# BOB_v1_03.net
KiCad netlist of a schematic drawn in EAGLE
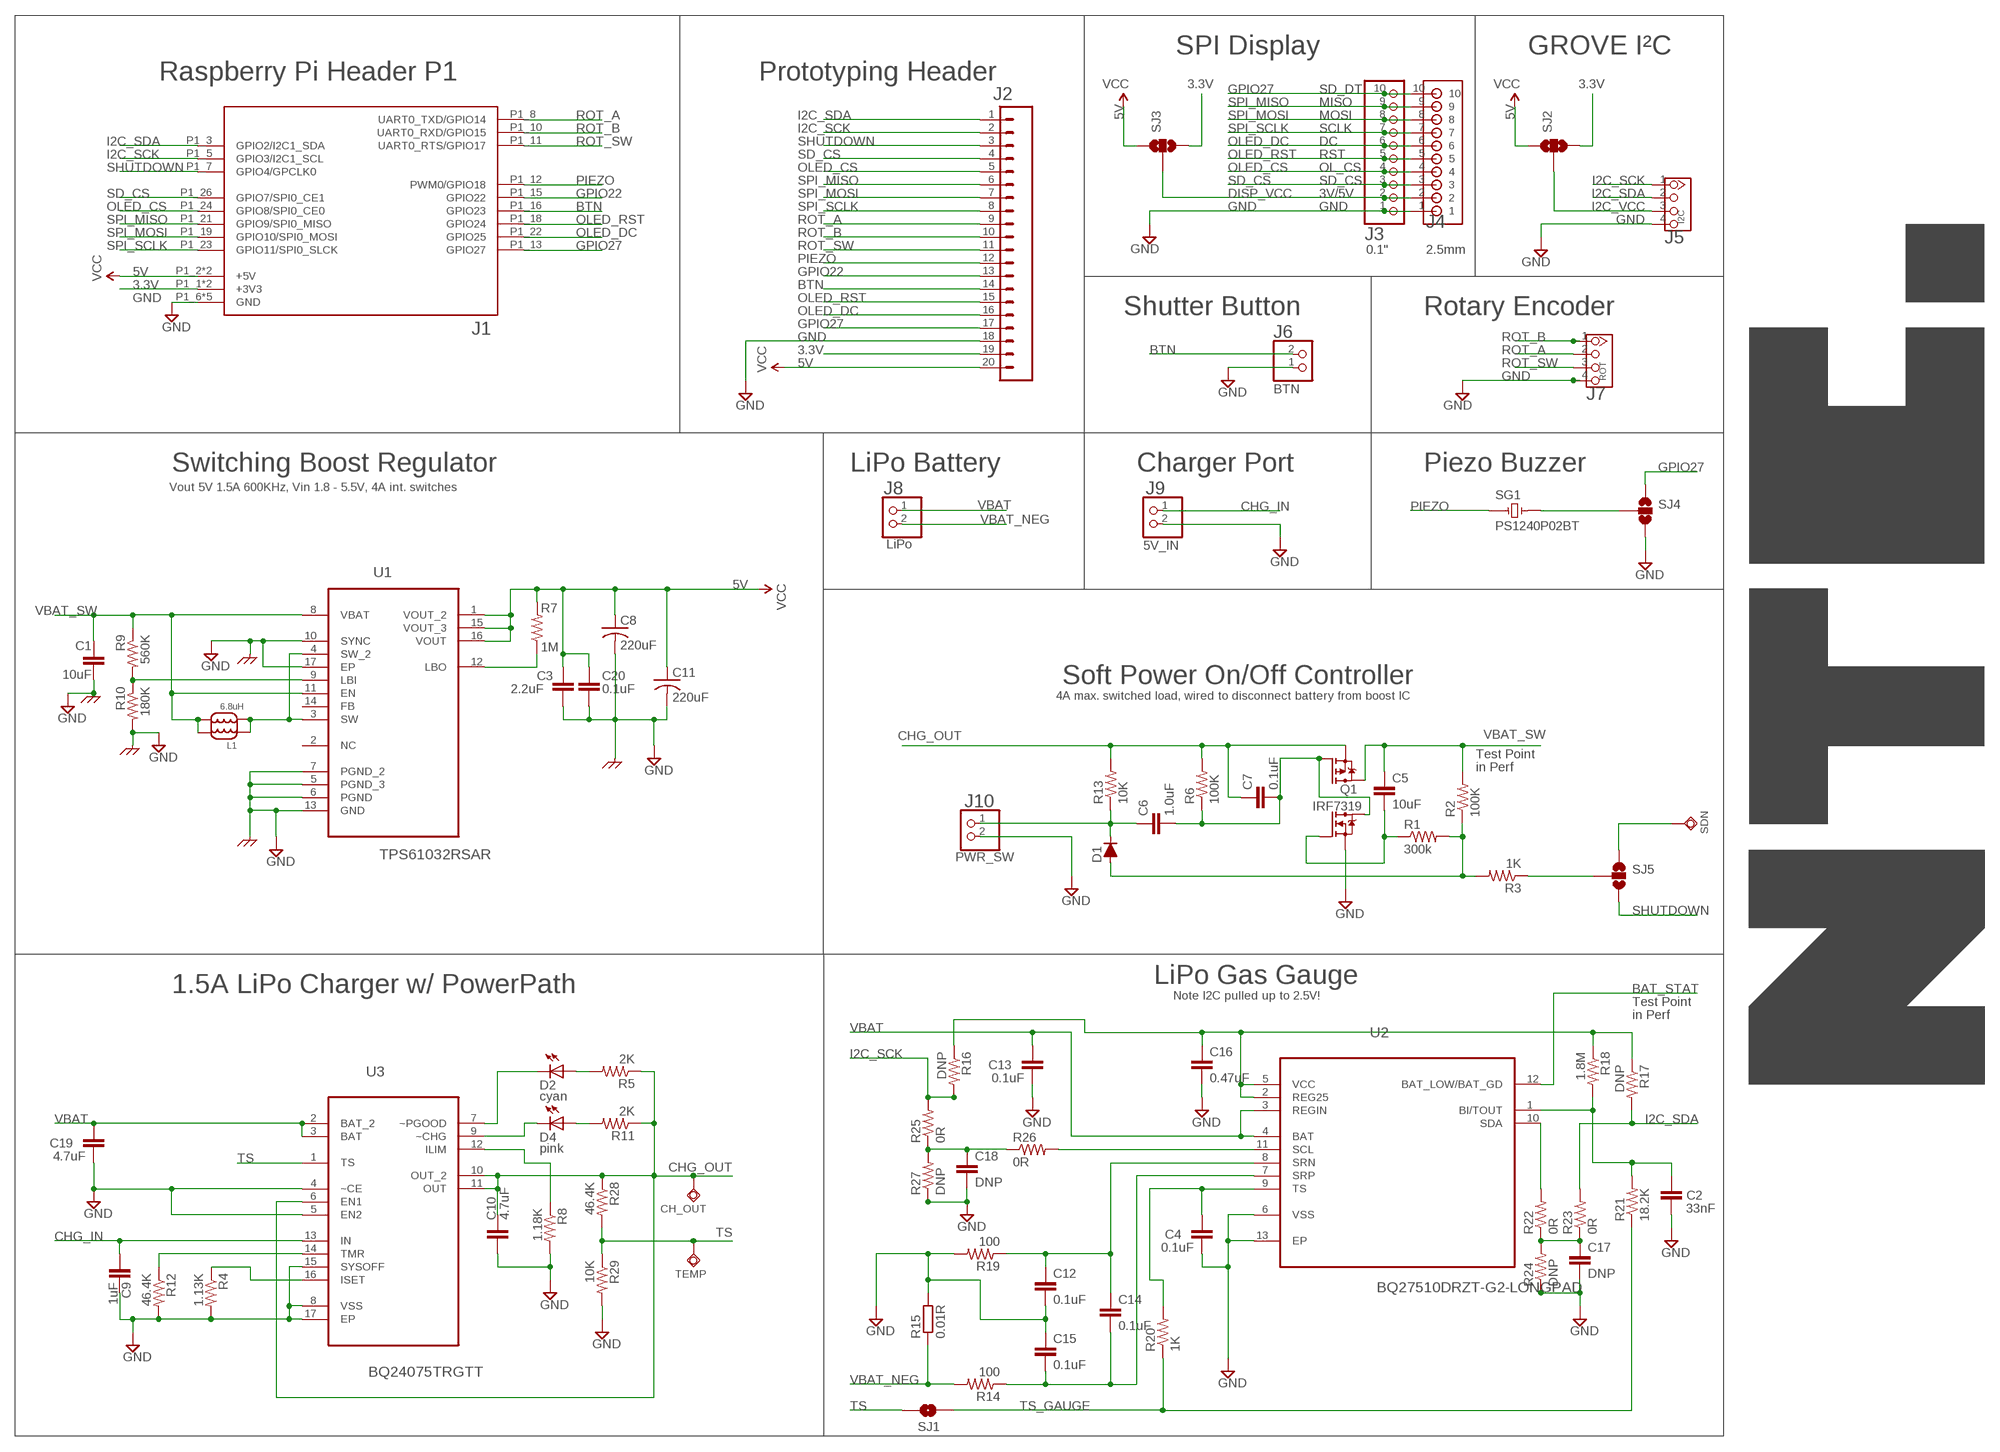
[diagram p0: schematic, sheet 1]

(export (version "E")
  (design (tool "Eeschema 10.0.6"))
  (components
    (comp (ref "C1")
      (value "10uF")
      (footprint "eagle-import:1206")
      (libsource (lib "eagle-import") (part "CAP1206"))
    )
    (comp (ref "C2")
      (value "33nF")
      (footprint "eagle-import:0603-CAP")
      (libsource (lib "eagle-import") (part "CAP0603-CAP"))
    )
    (comp (ref "C3")
      (value "2.2uF")
      (footprint "eagle-import:0603")
      (libsource (lib "eagle-import") (part "CAP0603"))
    )
    (comp (ref "C4")
      (value "0.1uF")
      (footprint "eagle-import:0603-CAP")
      (libsource (lib "eagle-import") (part "CAP0603-CAP"))
    )
    (comp (ref "C5")
      (value "10uF")
      (footprint "eagle-import:0603-CAP")
      (libsource (lib "eagle-import") (part "10UF-6.3V-20%(0603)"))
    )
    (comp (ref "C6")
      (value "1.0uF")
      (footprint "eagle-import:0603-CAP")
      (libsource (lib "eagle-import") (part "1.0UF-16V-10%(0603)"))
    )
    (comp (ref "C7")
      (value "0.1uF")
      (footprint "eagle-import:0603-CAP")
      (libsource (lib "eagle-import") (part "0.1UF-25V-5%(0603)"))
    )
    (comp (ref "C8")
      (value "220uF")
      (footprint "eagle-import:C1210")
      (libsource (lib "eagle-import") (part "C-USC1210"))
    )
    (comp (ref "C9")
      (value "1uF")
      (footprint "eagle-import:0603-CAP")
      (libsource (lib "eagle-import") (part "CAP0603-CAP"))
    )
    (comp (ref "C10")
      (value "4.7uF")
      (footprint "eagle-import:0603-CAP")
      (libsource (lib "eagle-import") (part "CAP0603-CAP"))
    )
    (comp (ref "C11")
      (value "220uF")
      (footprint "eagle-import:C1210")
      (libsource (lib "eagle-import") (part "C-USC1210"))
    )
    (comp (ref "C12")
      (value "0.1uF")
      (footprint "eagle-import:0603-CAP")
      (libsource (lib "eagle-import") (part "SparkFun-Capacitors_CAP0603-CAP"))
    )
    (comp (ref "C13")
      (value "0.1uF")
      (footprint "eagle-import:0603-CAP")
      (libsource (lib "eagle-import") (part "CAP0603-CAP"))
    )
    (comp (ref "C14")
      (value "0.1uF")
      (footprint "eagle-import:0603-CAP")
      (libsource (lib "eagle-import") (part "SparkFun-Capacitors_CAP0603-CAP"))
    )
    (comp (ref "C15")
      (value "0.1uF")
      (footprint "eagle-import:0603-CAP")
      (libsource (lib "eagle-import") (part "SparkFun-Capacitors_CAP0603-CAP"))
    )
    (comp (ref "C16")
      (value "0.47uF")
      (footprint "eagle-import:0603-CAP")
      (libsource (lib "eagle-import") (part "SparkFun-Capacitors_CAP0603-CAP"))
    )
    (comp (ref "C17")
      (value "DNP")
      (footprint "eagle-import:0603-CAP")
      (libsource (lib "eagle-import") (part "SparkFun-Capacitors_CAP0603-CAP"))
    )
    (comp (ref "C18")
      (value "DNP")
      (footprint "eagle-import:0603-CAP")
      (libsource (lib "eagle-import") (part "SparkFun-Capacitors_CAP0603-CAP"))
    )
    (comp (ref "C19")
      (value "4.7uF")
      (footprint "eagle-import:0603-CAP")
      (libsource (lib "eagle-import") (part "CAP0603-CAP"))
    )
    (comp (ref "C20")
      (value "0.1uF")
      (footprint "eagle-import:0603-CAP")
      (fields (field (name "PROD_ID") "CAP-00868"))
      (libsource (lib "eagle-import") (part "1.0UF-16V-10%(0603)"))
    )
    (comp (ref "CH_OUT")
      (value "TP1.2")
      (footprint "eagle-import:TP_1.2")
      (libsource (lib "eagle-import") (part "TP1.2"))
    )
    (comp (ref "D1")
      (value "D-FILL-SMB")
      (footprint "eagle-import:SMB")
      (libsource (lib "eagle-import") (part "D-FILL-SMB"))
    )
    (comp (ref "D2")
      (value "cyan")
      (footprint "eagle-import:LED-0603")
      (libsource (lib "eagle-import") (part "LED0603"))
    )
    (comp (ref "D4")
      (value "pink")
      (footprint "eagle-import:LED-0603")
      (libsource (lib "eagle-import") (part "LED0603"))
    )
    (comp (ref "J1")
      (value "PICAM_RPI-B-PICAM")
      (footprint "eagle-import:PICAM_RPI-B-PICAM")
      (libsource (lib "eagle-import") (part "PICAM_RPI-B-PICAM"))
    )
    (comp (ref "J2")
      (value "M20LOCK_LONGPADS")
      (footprint "eagle-import:1X20_LOCK_LONGPADS")
      (libsource (lib "eagle-import") (part "M20LOCK_LONGPADS"))
    )
    (comp (ref "J3")
      (value "PINHD-1X10")
      (footprint "eagle-import:1X10-BIG")
      (libsource (lib "eagle-import") (part "PINHD-1X10"))
    )
    (comp (ref "J4")
      (value "B10B-EH-A-RA")
      (footprint "eagle-import:S10B-EH")
      (libsource (lib "eagle-import") (part "B10B-EH-A-RA"))
    )
    (comp (ref "J5")
      (value "I2C")
      (footprint "eagle-import:CONNECTOR_4P-2.0-REVGND")
      (libsource (lib "eagle-import") (part "CONNECTOR_TWIG-4P-2.0"))
    )
    (comp (ref "J6")
      (value "BTN")
      (footprint "eagle-import:JST-PH-2-THM-REVGND")
      (libsource (lib "eagle-import") (part "JST_2PIN"))
    )
    (comp (ref "J7")
      (value "ROT")
      (footprint "eagle-import:CONNECTOR_4P-2.0-REVGND")
      (libsource (lib "eagle-import") (part "CONNECTOR_TWIG-4P-2.0"))
    )
    (comp (ref "J8")
      (value "LiPo")
      (footprint "eagle-import:PICAM_JST-PH-2-THM")
      (libsource (lib "eagle-import") (part "PICAM_JST_2PIN-THM"))
    )
    (comp (ref "J9")
      (value "5V_IN")
      (footprint "eagle-import:PICAM_JST-PH-2-THM")
      (libsource (lib "eagle-import") (part "PICAM_JST_2PIN-THM"))
    )
    (comp (ref "J10")
      (value "PWR_SW")
      (footprint "eagle-import:PICAM_JST-PH-2-THM")
      (libsource (lib "eagle-import") (part "PICAM_JST_2PIN-THM"))
    )
    (comp (ref "L1")
      (value "6.8uH")
      (footprint "eagle-import:SUMIDA_CDRH124")
      (libsource (lib "eagle-import") (part "SUMIDA_CDRH124CDRH124NP-6R8MC"))
    )
    (comp (ref "Q1")
      (value "IRF7319")
      (footprint "eagle-import:SO08-IRF")
      (libsource (lib "eagle-import") (part "IRF7319Q"))
    )
    (comp (ref "R1")
      (value "300k")
      (footprint "eagle-import:0603-RES")
      (libsource (lib "eagle-import") (part "SparkFun-Passives_RESISTOR0603-RES"))
    )
    (comp (ref "R2")
      (value "100K")
      (footprint "eagle-import:0603-RES")
      (libsource (lib "eagle-import") (part "SparkFun-Passives_RESISTOR0603-RES"))
    )
    (comp (ref "R3")
      (value "1K")
      (footprint "eagle-import:0603-RES")
      (libsource (lib "eagle-import") (part "SparkFun-Passives_RESISTOR0603-RES"))
    )
    (comp (ref "R4")
      (value "1.13K")
      (footprint "eagle-import:0603-RES")
      (libsource (lib "eagle-import") (part "RESISTOR0603-RES"))
    )
    (comp (ref "R5")
      (value "2K")
      (footprint "eagle-import:0603-RES")
      (libsource (lib "eagle-import") (part "RESISTOR0603-RES"))
    )
    (comp (ref "R6")
      (value "100K")
      (footprint "eagle-import:0603-RES")
      (libsource (lib "eagle-import") (part "SparkFun-Passives_RESISTOR0603-RES"))
    )
    (comp (ref "R7")
      (value "1M")
      (footprint "eagle-import:0603-RES")
      (libsource (lib "eagle-import") (part "RESISTOR0603-RES"))
    )
    (comp (ref "R8")
      (value "1.18K")
      (footprint "eagle-import:0603-RES")
      (libsource (lib "eagle-import") (part "RESISTOR0603-RES"))
    )
    (comp (ref "R9")
      (value "560K")
      (footprint "eagle-import:0603-RES")
      (libsource (lib "eagle-import") (part "RESISTOR0603-RES"))
    )
    (comp (ref "R10")
      (value "180K")
      (footprint "eagle-import:0603-RES")
      (libsource (lib "eagle-import") (part "RESISTOR0603-RES"))
    )
    (comp (ref "R11")
      (value "2K")
      (footprint "eagle-import:0603-RES")
      (libsource (lib "eagle-import") (part "RESISTOR0603-RES"))
    )
    (comp (ref "R12")
      (value "46.4K")
      (footprint "eagle-import:0603-RES")
      (libsource (lib "eagle-import") (part "RESISTOR0603-RES"))
    )
    (comp (ref "R13")
      (value "10K")
      (footprint "eagle-import:0603-RES")
      (libsource (lib "eagle-import") (part "SparkFun-Passives_RESISTOR0603-RES"))
    )
    (comp (ref "R14")
      (value "100")
      (footprint "eagle-import:0603-RES")
      (libsource (lib "eagle-import") (part "RESISTOR0603-RES"))
    )
    (comp (ref "R15")
      (value "0.01R")
      (footprint "eagle-import:R1206")
      (libsource (lib "eagle-import") (part "RESISTOR-1206"))
    )
    (comp (ref "R16")
      (value "DNP")
      (footprint "eagle-import:0603-RES")
      (libsource (lib "eagle-import") (part "RESISTOR0603-RES"))
    )
    (comp (ref "R17")
      (value "DNP")
      (footprint "eagle-import:0603-RES")
      (libsource (lib "eagle-import") (part "RESISTOR0603-RES"))
    )
    (comp (ref "R18")
      (value "1.8M")
      (footprint "eagle-import:0603-RES")
      (libsource (lib "eagle-import") (part "RESISTOR0603-RES"))
    )
    (comp (ref "R19")
      (value "100")
      (footprint "eagle-import:0603-RES")
      (libsource (lib "eagle-import") (part "RESISTOR0603-RES"))
    )
    (comp (ref "R20")
      (value "1K")
      (footprint "eagle-import:0603-RES")
      (libsource (lib "eagle-import") (part "SparkFun-Resistors_RESISTOR0603-RES"))
    )
    (comp (ref "R21")
      (value "18.2K")
      (footprint "eagle-import:0603-RES")
      (libsource (lib "eagle-import") (part "SparkFun-Resistors_RESISTOR0603-RES"))
    )
    (comp (ref "R22")
      (value "0R")
      (footprint "eagle-import:0603-RES")
      (libsource (lib "eagle-import") (part "SparkFun-Resistors_RESISTOR0603-RES"))
    )
    (comp (ref "R23")
      (value "0R")
      (footprint "eagle-import:0603-RES")
      (libsource (lib "eagle-import") (part "SparkFun-Resistors_RESISTOR0603-RES"))
    )
    (comp (ref "R24")
      (value "DNP")
      (footprint "eagle-import:0603-RES")
      (libsource (lib "eagle-import") (part "SparkFun-Resistors_RESISTOR0603-RES"))
    )
    (comp (ref "R25")
      (value "0R")
      (footprint "eagle-import:0603-RES")
      (libsource (lib "eagle-import") (part "SparkFun-Resistors_RESISTOR0603-RES"))
    )
    (comp (ref "R26")
      (value "0R")
      (footprint "eagle-import:0603-RES")
      (libsource (lib "eagle-import") (part "SparkFun-Resistors_RESISTOR0603-RES"))
    )
    (comp (ref "R27")
      (value "DNP")
      (footprint "eagle-import:0603-RES")
      (libsource (lib "eagle-import") (part "SparkFun-Resistors_RESISTOR0603-RES"))
    )
    (comp (ref "R28")
      (value "46.4K")
      (footprint "eagle-import:0603-RES")
      (libsource (lib "eagle-import") (part "RESISTOR0603-RES"))
    )
    (comp (ref "R29")
      (value "10K")
      (footprint "eagle-import:0603-RES")
      (libsource (lib "eagle-import") (part "RESISTOR0603-RES"))
    )
    (comp (ref "SDN")
      (value "TP1.2")
      (footprint "eagle-import:TP_1.2")
      (libsource (lib "eagle-import") (part "TP1.2"))
    )
    (comp (ref "SG1")
      (value "PS1240P02BT")
      (footprint "eagle-import:PS1240")
      (libsource (lib "eagle-import") (part "PS1240P02BT"))
    )
    (comp (ref "SJ1")
      (value "SOLDERJUMPER-OLDTRACE")
      (footprint "eagle-import:SJ_2S-TRACE")
      (libsource (lib "eagle-import") (part "SOLDERJUMPER-OLDTRACE"))
    )
    (comp (ref "SJ2")
      (value "SOLDERJUMPER_2WAYPASTE1&2")
      (footprint "eagle-import:SJ_3_PASTE1&2")
      (libsource (lib "eagle-import") (part "SOLDERJUMPER_2WAYPASTE1&2"))
    )
    (comp (ref "SJ3")
      (value "SOLDERJUMPER_2WAYPASTE2&3")
      (footprint "eagle-import:SJ_3_PASTE2&3")
      (libsource (lib "eagle-import") (part "SOLDERJUMPER_2WAYPASTE2&3"))
    )
    (comp (ref "SJ4")
      (value "SOLDERJUMPER_2WAYPASTE1&2")
      (footprint "eagle-import:SJ_3_PASTE1&2")
      (libsource (lib "eagle-import") (part "SOLDERJUMPER_2WAYPASTE1&2"))
    )
    (comp (ref "SJ5")
      (value "SOLDERJUMPER_2WAYPASTE2&3")
      (footprint "eagle-import:SJ_3_PASTE2&3")
      (libsource (lib "eagle-import") (part "SOLDERJUMPER_2WAYPASTE2&3"))
    )
    (comp (ref "TEMP")
      (value "TP1.2")
      (footprint "eagle-import:TP_1.2")
      (libsource (lib "eagle-import") (part "TP1.2"))
    )
    (comp (ref "U1")
      (value "TPS61032RSAR")
      (footprint "eagle-import:QFN65P400X400X100-17N")
      (libsource (lib "eagle-import") (part "TPS61032RSAR"))
    )
    (comp (ref "U2")
      (value "BQ27510DRZT-G2-LONGPAD")
      (footprint "eagle-import:SON40P400X250X100-13N+LONGPAD")
      (fields (field (name "MPN") "BQ27510DRZT-G2") (field (name "SUPPLIER") "Texas Inustruments"))
      (libsource (lib "eagle-import") (part "BQ27510DRZT-G2-LONGPAD"))
    )
    (comp (ref "U3")
      (value "BQ24075TRGTT")
      (footprint "eagle-import:QFN50P300X300X100-17N")
      (libsource (lib "eagle-import") (part "BQ24075TRGTT"))
    )
  )
  (nets
    (net (code "1") (name "3.3V") (class "Default")
      (node (ref "J1") (pin "P1_1") (pinfunction "+3V3_P1_1") (pintype "power_in"))
      (node (ref "J1") (pin "P1_17") (pinfunction "+3V3_P1_17") (pintype "power_in"))
      (node (ref "J2") (pin "19") (pinfunction "19_19") (pintype "passive"))
      (node (ref "SJ2") (pin "3") (pinfunction "3_3") (pintype "passive"))
      (node (ref "SJ3") (pin "3") (pinfunction "3_3") (pintype "passive"))
    )
    (net (code "2") (name "5V") (class "Default")
      (node (ref "C11") (pin "1") (pinfunction "1_1") (pintype "passive"))
      (node (ref "C20") (pin "1") (pinfunction "1_1") (pintype "passive"))
      (node (ref "C3") (pin "1") (pinfunction "1_1") (pintype "passive"))
      (node (ref "C8") (pin "1") (pinfunction "1_1") (pintype "passive"))
      (node (ref "J1") (pin "P1_2") (pinfunction "+5V_P1_2") (pintype "power_in"))
      (node (ref "J1") (pin "P1_4") (pinfunction "+5V_P1_4") (pintype "power_in"))
      (node (ref "J2") (pin "20") (pinfunction "20_20") (pintype "passive"))
      (node (ref "R7") (pin "2") (pinfunction "2_2") (pintype "passive"))
      (node (ref "SJ2") (pin "1") (pinfunction "1_1") (pintype "passive"))
      (node (ref "SJ3") (pin "1") (pinfunction "1_1") (pintype "passive"))
      (node (ref "U1") (pin "1") (pinfunction "VOUT_2_1") (pintype "output"))
      (node (ref "U1") (pin "15") (pinfunction "VOUT_3_15") (pintype "output"))
      (node (ref "U1") (pin "16") (pinfunction "VOUT_16") (pintype "output"))
    )
    (net (code "3") (name "BAT_STAT") (class "Default")
      (node (ref "U2") (pin "12") (pinfunction "BAT_LOW/BAT_GD_12") (pintype "output"))
    )
    (net (code "4") (name "BTN") (class "Default")
      (node (ref "J1") (pin "P1_16") (pinfunction "GPIO23_P1_16") (pintype "bidirectional"))
      (node (ref "J2") (pin "14") (pinfunction "14_14") (pintype "passive"))
      (node (ref "J6") (pin "2") (pinfunction "1_2") (pintype "passive"))
    )
    (net (code "5") (name "CHG_IN") (class "Default")
      (node (ref "C9") (pin "1") (pinfunction "1_1") (pintype "passive"))
      (node (ref "J9") (pin "1") (pinfunction "2_1") (pintype "passive"))
      (node (ref "U3") (pin "13") (pinfunction "IN_13") (pintype "input"))
    )
    (net (code "6") (name "CHG_OUT") (class "Default")
      (node (ref "C10") (pin "1") (pinfunction "1_1") (pintype "passive"))
      (node (ref "C7") (pin "1") (pinfunction "1_1") (pintype "passive"))
      (node (ref "CH_OUT") (pin "1") (pinfunction "TP_1") (pintype "passive"))
      (node (ref "Q1") (pin "3") (pinfunction "P-S2_3") (pintype "passive"))
      (node (ref "R11") (pin "1") (pinfunction "1_1") (pintype "passive"))
      (node (ref "R13") (pin "2") (pinfunction "2_2") (pintype "passive"))
      (node (ref "R28") (pin "1") (pinfunction "1_1") (pintype "passive"))
      (node (ref "R5") (pin "1") (pinfunction "1_1") (pintype "passive"))
      (node (ref "R6") (pin "2") (pinfunction "2_2") (pintype "passive"))
      (node (ref "U3") (pin "10") (pinfunction "OUT_2_10") (pintype "output"))
      (node (ref "U3") (pin "11") (pinfunction "OUT_11") (pintype "output"))
      (node (ref "U3") (pin "6") (pinfunction "EN1_6") (pintype "input"))
    )
    (net (code "7") (name "DISP_VCC") (class "Default")
      (node (ref "J3") (pin "2") (pinfunction "2_2") (pintype "passive"))
      (node (ref "J4") (pin "2") (pinfunction "2_2") (pintype "bidirectional"))
      (node (ref "SJ3") (pin "2") (pinfunction "2_2") (pintype "passive"))
    )
    (net (code "8") (name "GND") (class "Default")
      (node (ref "C1") (pin "2") (pinfunction "2_2") (pintype "passive"))
      (node (ref "C10") (pin "2") (pinfunction "2_2") (pintype "passive"))
      (node (ref "C11") (pin "2") (pinfunction "2_2") (pintype "passive"))
      (node (ref "C12") (pin "2") (pinfunction "2_2") (pintype "passive"))
      (node (ref "C13") (pin "2") (pinfunction "2_2") (pintype "passive"))
      (node (ref "C15") (pin "1") (pinfunction "1_1") (pintype "passive"))
      (node (ref "C16") (pin "2") (pinfunction "2_2") (pintype "passive"))
      (node (ref "C17") (pin "2") (pinfunction "2_2") (pintype "passive"))
      (node (ref "C18") (pin "2") (pinfunction "2_2") (pintype "passive"))
      (node (ref "C19") (pin "2") (pinfunction "2_2") (pintype "passive"))
      (node (ref "C2") (pin "2") (pinfunction "2_2") (pintype "passive"))
      (node (ref "C20") (pin "2") (pinfunction "2_2") (pintype "passive"))
      (node (ref "C3") (pin "2") (pinfunction "2_2") (pintype "passive"))
      (node (ref "C4") (pin "2") (pinfunction "2_2") (pintype "passive"))
      (node (ref "C8") (pin "2") (pinfunction "2_2") (pintype "passive"))
      (node (ref "C9") (pin "2") (pinfunction "2_2") (pintype "passive"))
      (node (ref "J1") (pin "P1_14") (pinfunction "GND_P1_14") (pintype "power_in"))
      (node (ref "J1") (pin "P1_20") (pinfunction "GND_P1_20") (pintype "power_in"))
      (node (ref "J1") (pin "P1_25") (pinfunction "GND_P1_25") (pintype "power_in"))
      (node (ref "J1") (pin "P1_6") (pinfunction "GND_P1_6") (pintype "power_in"))
      (node (ref "J1") (pin "P1_9") (pinfunction "GND_P1_9") (pintype "power_in"))
      (node (ref "J10") (pin "2") (pinfunction "1_2") (pintype "passive"))
      (node (ref "J2") (pin "18") (pinfunction "18_18") (pintype "passive"))
      (node (ref "J3") (pin "1") (pinfunction "1_1") (pintype "passive"))
      (node (ref "J4") (pin "1") (pinfunction "1_1") (pintype "bidirectional"))
      (node (ref "J5") (pin "4") (pinfunction "4_4") (pintype "bidirectional"))
      (node (ref "J6") (pin "1") (pinfunction "2_1") (pintype "passive"))
      (node (ref "J7") (pin "4") (pinfunction "4_4") (pintype "bidirectional"))
      (node (ref "J9") (pin "2") (pinfunction "1_2") (pintype "passive"))
      (node (ref "Q1") (pin "1") (pinfunction "N-S1_1") (pintype "passive"))
      (node (ref "R10") (pin "2") (pinfunction "2_2") (pintype "passive"))
      (node (ref "R12") (pin "2") (pinfunction "2_2") (pintype "passive"))
      (node (ref "R15") (pin "2") (pinfunction "2_2") (pintype "passive"))
      (node (ref "R19") (pin "2") (pinfunction "2_2") (pintype "passive"))
      (node (ref "R24") (pin "1") (pinfunction "1_1") (pintype "passive"))
      (node (ref "R27") (pin "1") (pinfunction "1_1") (pintype "passive"))
      (node (ref "R29") (pin "2") (pinfunction "2_2") (pintype "passive"))
      (node (ref "R4") (pin "2") (pinfunction "2_2") (pintype "passive"))
      (node (ref "R8") (pin "2") (pinfunction "2_2") (pintype "passive"))
      (node (ref "SJ4") (pin "3") (pinfunction "3_3") (pintype "passive"))
      (node (ref "U1") (pin "10") (pinfunction "SYNC_10") (pintype "input"))
      (node (ref "U1") (pin "13") (pinfunction "GND_13") (pintype "passive"))
      (node (ref "U1") (pin "17") (pinfunction "EP_17") (pintype "passive"))
      (node (ref "U1") (pin "5") (pinfunction "PGND_3_5") (pintype "passive"))
      (node (ref "U1") (pin "6") (pinfunction "PGND_6") (pintype "passive"))
      (node (ref "U1") (pin "7") (pinfunction "PGND_2_7") (pintype "passive"))
      (node (ref "U2") (pin "13") (pinfunction "EP_13") (pintype "passive"))
      (node (ref "U2") (pin "6") (pinfunction "VSS_6") (pintype "power_in"))
      (node (ref "U3") (pin "15") (pinfunction "SYSOFF_15") (pintype "input"))
      (node (ref "U3") (pin "17") (pinfunction "EP_17") (pintype "passive"))
      (node (ref "U3") (pin "4") (pinfunction "~{CE}_4") (pintype "input"))
      (node (ref "U3") (pin "5") (pinfunction "EN2_5") (pintype "input"))
      (node (ref "U3") (pin "8") (pinfunction "VSS_8") (pintype "passive"))
    )
    (net (code "9") (name "GPIO22") (class "Default")
      (node (ref "J1") (pin "P1_15") (pinfunction "GPIO22_P1_15") (pintype "bidirectional"))
      (node (ref "J2") (pin "13") (pinfunction "13_13") (pintype "passive"))
    )
    (net (code "10") (name "GPIO27") (class "Default")
      (node (ref "J1") (pin "P1_13") (pinfunction "GPIO27_P1_13") (pintype "bidirectional"))
      (node (ref "J2") (pin "17") (pinfunction "17_17") (pintype "passive"))
      (node (ref "J3") (pin "10") (pinfunction "10_10") (pintype "passive"))
      (node (ref "J4") (pin "10") (pinfunction "10_10") (pintype "bidirectional"))
      (node (ref "SJ4") (pin "1") (pinfunction "1_1") (pintype "passive"))
    )
    (net (code "11") (name "I2C_SCK") (class "Default")
      (node (ref "J1") (pin "P1_5") (pinfunction "GPIO3/I2C1_SCL_P1_5") (pintype "bidirectional"))
      (node (ref "J2") (pin "2") (pinfunction "2_2") (pintype "passive"))
      (node (ref "J5") (pin "1") (pinfunction "1_1") (pintype "bidirectional"))
      (node (ref "R16") (pin "2") (pinfunction "2_2") (pintype "passive"))
      (node (ref "R25") (pin "2") (pinfunction "2_2") (pintype "passive"))
    )
    (net (code "12") (name "I2C_SDA") (class "Default")
      (node (ref "J1") (pin "P1_3") (pinfunction "GPIO2/I2C1_SDA_P1_3") (pintype "bidirectional"))
      (node (ref "J2") (pin "1") (pinfunction "1_1") (pintype "passive"))
      (node (ref "J5") (pin "2") (pinfunction "2_2") (pintype "bidirectional"))
      (node (ref "R17") (pin "2") (pinfunction "2_2") (pintype "passive"))
      (node (ref "R23") (pin "2") (pinfunction "2_2") (pintype "passive"))
    )
    (net (code "13") (name "I2C_VCC") (class "Default")
      (node (ref "J5") (pin "3") (pinfunction "3_3") (pintype "bidirectional"))
      (node (ref "SJ2") (pin "2") (pinfunction "2_2") (pintype "passive"))
    )
    (net (code "14") (name "Net-(C17-Pad1)") (class "Default")
      (node (ref "C17") (pin "1") (pinfunction "1_1") (pintype "passive"))
      (node (ref "R22") (pin "1") (pinfunction "1_1") (pintype "passive"))
      (node (ref "R23") (pin "1") (pinfunction "1_1") (pintype "passive"))
      (node (ref "R24") (pin "2") (pinfunction "2_2") (pintype "passive"))
    )
    (net (code "15") (name "Net-(C18-Pad1)") (class "Default")
      (node (ref "C18") (pin "1") (pinfunction "1_1") (pintype "passive"))
      (node (ref "R25") (pin "1") (pinfunction "1_1") (pintype "passive"))
      (node (ref "R26") (pin "1") (pinfunction "1_1") (pintype "passive"))
      (node (ref "R27") (pin "2") (pinfunction "2_2") (pintype "passive"))
    )
    (net (code "16") (name "Net-(D1-A)") (class "Default")
      (node (ref "D1") (pin "2") (pinfunction "A_2") (pintype "passive"))
      (node (ref "R1") (pin "2") (pinfunction "2_2") (pintype "passive"))
      (node (ref "R2") (pin "1") (pinfunction "1_1") (pintype "passive"))
      (node (ref "R3") (pin "2") (pinfunction "2_2") (pintype "passive"))
    )
    (net (code "17") (name "Net-(D1-C)") (class "Default")
      (node (ref "C6") (pin "1") (pinfunction "1_1") (pintype "passive"))
      (node (ref "D1") (pin "1") (pinfunction "C_1") (pintype "passive"))
      (node (ref "J10") (pin "1") (pinfunction "2_1") (pintype "passive"))
      (node (ref "R13") (pin "1") (pinfunction "1_1") (pintype "passive"))
    )
    (net (code "18") (name "Net-(D2-PadA)") (class "Default")
      (node (ref "D2") (pin "A") (pinfunction "A_A") (pintype "passive"))
      (node (ref "R5") (pin "2") (pinfunction "2_2") (pintype "passive"))
    )
    (net (code "19") (name "Net-(D4-PadA)") (class "Default")
      (node (ref "D4") (pin "A") (pinfunction "A_A") (pintype "passive"))
      (node (ref "R11") (pin "2") (pinfunction "2_2") (pintype "passive"))
    )
    (net (code "20") (name "Net-(Q1-N-G1)") (class "Default")
      (node (ref "C5") (pin "2") (pinfunction "2_2") (pintype "passive"))
      (node (ref "Q1") (pin "2") (pinfunction "N-G1_2") (pintype "passive"))
      (node (ref "R1") (pin "1") (pinfunction "1_1") (pintype "passive"))
    )
    (net (code "21") (name "Net-(Q1-P-G2)") (class "Default")
      (node (ref "C6") (pin "2") (pinfunction "2_2") (pintype "passive"))
      (node (ref "C7") (pin "2") (pinfunction "2_2") (pintype "passive"))
      (node (ref "Q1") (pin "4") (pinfunction "P-G2_4") (pintype "passive"))
      (node (ref "Q1") (pin "7") (pinfunction "N-D1_7") (pintype "passive"))
      (node (ref "Q1") (pin "8") (pinfunction "N-D1_8") (pintype "passive"))
      (node (ref "R6") (pin "1") (pinfunction "1_1") (pintype "passive"))
    )
    (net (code "22") (name "Net-(R3-Pad1)") (class "Default")
      (node (ref "R3") (pin "1") (pinfunction "1_1") (pintype "passive"))
      (node (ref "SJ5") (pin "2") (pinfunction "2_2") (pintype "passive"))
    )
    (net (code "23") (name "Net-(SDN-TP)") (class "Default")
      (node (ref "SDN") (pin "1") (pinfunction "TP_1") (pintype "passive"))
      (node (ref "SJ5") (pin "1") (pinfunction "1_1") (pintype "passive"))
    )
    (net (code "24") (name "Net-(SG1-2)") (class "Default")
      (node (ref "SG1") (pin "P$2") (pinfunction "2_P$2") (pintype "passive"))
      (node (ref "SJ4") (pin "2") (pinfunction "2_2") (pintype "passive"))
    )
    (net (code "25") (name "Net-(U1-LBI)") (class "Default")
      (node (ref "R10") (pin "1") (pinfunction "1_1") (pintype "passive"))
      (node (ref "R9") (pin "2") (pinfunction "2_2") (pintype "passive"))
      (node (ref "U1") (pin "9") (pinfunction "LBI_9") (pintype "input"))
    )
    (net (code "26") (name "Net-(U1-LBO)") (class "Default")
      (node (ref "R7") (pin "1") (pinfunction "1_1") (pintype "passive"))
      (node (ref "U1") (pin "12") (pinfunction "LBO_12") (pintype "output"))
    )
    (net (code "27") (name "Net-(U1-SW)") (class "Default")
      (node (ref "L1") (pin "P$3") (pinfunction "2_P$3") (pintype "passive"))
      (node (ref "L1") (pin "P$4") (pinfunction "2_P$4") (pintype "passive"))
      (node (ref "U1") (pin "3") (pinfunction "SW_3") (pintype "input"))
      (node (ref "U1") (pin "4") (pinfunction "SW_2_4") (pintype "input"))
    )
    (net (code "28") (name "Net-(U2-BI{slash}TOUT)") (class "Default")
      (node (ref "C2") (pin "1") (pinfunction "1_1") (pintype "passive"))
      (node (ref "R18") (pin "2") (pinfunction "2_2") (pintype "passive"))
      (node (ref "R21") (pin "2") (pinfunction "2_2") (pintype "passive"))
      (node (ref "U2") (pin "1") (pinfunction "BI/TOUT_1") (pintype "bidirectional"))
    )
    (net (code "29") (name "Net-(U2-REG25)") (class "Default")
      (node (ref "C16") (pin "1") (pinfunction "1_1") (pintype "passive"))
      (node (ref "R16") (pin "1") (pinfunction "1_1") (pintype "passive"))
      (node (ref "R17") (pin "1") (pinfunction "1_1") (pintype "passive"))
      (node (ref "R18") (pin "1") (pinfunction "1_1") (pintype "passive"))
      (node (ref "U2") (pin "2") (pinfunction "REG25_2") (pintype "power_in"))
      (node (ref "U2") (pin "5") (pinfunction "VCC_5") (pintype "power_in"))
    )
    (net (code "30") (name "Net-(U2-SCL)") (class "Default")
      (node (ref "R26") (pin "2") (pinfunction "2_2") (pintype "passive"))
      (node (ref "U2") (pin "11") (pinfunction "SCL_11") (pintype "input"))
    )
    (net (code "31") (name "Net-(U2-SDA)") (class "Default")
      (node (ref "R22") (pin "2") (pinfunction "2_2") (pintype "passive"))
      (node (ref "U2") (pin "10") (pinfunction "SDA_10") (pintype "bidirectional"))
    )
    (net (code "32") (name "Net-(U2-SRN)") (class "Default")
      (node (ref "C12") (pin "1") (pinfunction "1_1") (pintype "passive"))
      (node (ref "C14") (pin "1") (pinfunction "1_1") (pintype "passive"))
      (node (ref "R19") (pin "1") (pinfunction "1_1") (pintype "passive"))
      (node (ref "U2") (pin "8") (pinfunction "SRN_8") (pintype "input"))
    )
    (net (code "33") (name "Net-(U2-SRP)") (class "Default")
      (node (ref "C14") (pin "2") (pinfunction "2_2") (pintype "passive"))
      (node (ref "C15") (pin "2") (pinfunction "2_2") (pintype "passive"))
      (node (ref "R14") (pin "1") (pinfunction "1_1") (pintype "passive"))
      (node (ref "U2") (pin "7") (pinfunction "SRP_7") (pintype "input"))
    )
    (net (code "34") (name "Net-(U2-TS)") (class "Default")
      (node (ref "C4") (pin "1") (pinfunction "1_1") (pintype "passive"))
      (node (ref "R20") (pin "2") (pinfunction "2_2") (pintype "passive"))
      (node (ref "U2") (pin "9") (pinfunction "TS_9") (pintype "input"))
    )
    (net (code "35") (name "Net-(U3-ILIM)") (class "Default")
      (node (ref "R8") (pin "1") (pinfunction "1_1") (pintype "passive"))
      (node (ref "U3") (pin "12") (pinfunction "ILIM_12") (pintype "output"))
    )
    (net (code "36") (name "Net-(U3-ISET)") (class "Default")
      (node (ref "R4") (pin "1") (pinfunction "1_1") (pintype "passive"))
      (node (ref "U3") (pin "16") (pinfunction "ISET_16") (pintype "bidirectional"))
    )
    (net (code "37") (name "Net-(U3-TMR)") (class "Default")
      (node (ref "R12") (pin "1") (pinfunction "1_1") (pintype "passive"))
      (node (ref "U3") (pin "14") (pinfunction "TMR_14") (pintype "input"))
    )
    (net (code "38") (name "Net-(U3-~{CHG})") (class "Default")
      (node (ref "D4") (pin "C") (pinfunction "C_C") (pintype "passive"))
      (node (ref "U3") (pin "9") (pinfunction "~{CHG}_9") (pintype "output"))
    )
    (net (code "39") (name "Net-(U3-~{PGOOD})") (class "Default")
      (node (ref "D2") (pin "C") (pinfunction "C_C") (pintype "passive"))
      (node (ref "U3") (pin "7") (pinfunction "~{PGOOD}_7") (pintype "output"))
    )
    (net (code "40") (name "OLED_CS") (class "Default")
      (node (ref "J1") (pin "P1_24") (pinfunction "GPIO8/SPI0_CE0_P1_24") (pintype "bidirectional"))
      (node (ref "J2") (pin "5") (pinfunction "5_5") (pintype "passive"))
      (node (ref "J3") (pin "4") (pinfunction "4_4") (pintype "passive"))
      (node (ref "J4") (pin "4") (pinfunction "4_4") (pintype "bidirectional"))
    )
    (net (code "41") (name "OLED_DC") (class "Default")
      (node (ref "J1") (pin "P1_22") (pinfunction "GPIO25_P1_22") (pintype "bidirectional"))
      (node (ref "J2") (pin "16") (pinfunction "16_16") (pintype "passive"))
      (node (ref "J3") (pin "6") (pinfunction "6_6") (pintype "passive"))
      (node (ref "J4") (pin "6") (pinfunction "6_6") (pintype "bidirectional"))
    )
    (net (code "42") (name "OLED_RST") (class "Default")
      (node (ref "J1") (pin "P1_18") (pinfunction "GPIO24_P1_18") (pintype "bidirectional"))
      (node (ref "J2") (pin "15") (pinfunction "15_15") (pintype "passive"))
      (node (ref "J3") (pin "5") (pinfunction "5_5") (pintype "passive"))
      (node (ref "J4") (pin "5") (pinfunction "5_5") (pintype "bidirectional"))
    )
    (net (code "43") (name "PIEZO") (class "Default")
      (node (ref "J1") (pin "P1_12") (pinfunction "PWM0/GPIO18_P1_12") (pintype "bidirectional"))
      (node (ref "J2") (pin "12") (pinfunction "12_12") (pintype "passive"))
      (node (ref "SG1") (pin "P$1") (pinfunction "1_P$1") (pintype "passive"))
    )
    (net (code "44") (name "ROT_A") (class "Default")
      (node (ref "J1") (pin "P1_8") (pinfunction "UART0_TXD/GPIO14_P1_8") (pintype "bidirectional"))
      (node (ref "J2") (pin "9") (pinfunction "9_9") (pintype "passive"))
      (node (ref "J7") (pin "2") (pinfunction "2_2") (pintype "bidirectional"))
    )
    (net (code "45") (name "ROT_B") (class "Default")
      (node (ref "J1") (pin "P1_10") (pinfunction "UART0_RXD/GPIO15_P1_10") (pintype "bidirectional"))
      (node (ref "J2") (pin "10") (pinfunction "10_10") (pintype "passive"))
      (node (ref "J7") (pin "1") (pinfunction "1_1") (pintype "bidirectional"))
    )
    (net (code "46") (name "ROT_SW") (class "Default")
      (node (ref "J1") (pin "P1_11") (pinfunction "UART0_RTS/GPIO17_P1_11") (pintype "bidirectional"))
      (node (ref "J2") (pin "11") (pinfunction "11_11") (pintype "passive"))
      (node (ref "J7") (pin "3") (pinfunction "3_3") (pintype "bidirectional"))
    )
    (net (code "47") (name "SD_CS") (class "Default")
      (node (ref "J1") (pin "P1_26") (pinfunction "GPIO7/SPI0_CE1_P1_26") (pintype "bidirectional"))
      (node (ref "J2") (pin "4") (pinfunction "4_4") (pintype "passive"))
      (node (ref "J3") (pin "3") (pinfunction "3_3") (pintype "passive"))
      (node (ref "J4") (pin "3") (pinfunction "3_3") (pintype "bidirectional"))
    )
    (net (code "48") (name "SHUTDOWN") (class "Default")
      (node (ref "J1") (pin "P1_7") (pinfunction "GPIO4/GPCLK0_P1_7") (pintype "bidirectional"))
      (node (ref "J2") (pin "3") (pinfunction "3_3") (pintype "passive"))
      (node (ref "SJ5") (pin "3") (pinfunction "3_3") (pintype "passive"))
    )
    (net (code "49") (name "SPI_MISO") (class "Default")
      (node (ref "J1") (pin "P1_21") (pinfunction "GPIO9/SPI0_MISO_P1_21") (pintype "bidirectional"))
      (node (ref "J2") (pin "6") (pinfunction "6_6") (pintype "passive"))
      (node (ref "J3") (pin "9") (pinfunction "9_9") (pintype "passive"))
      (node (ref "J4") (pin "9") (pinfunction "9_9") (pintype "bidirectional"))
    )
    (net (code "50") (name "SPI_MOSI") (class "Default")
      (node (ref "J1") (pin "P1_19") (pinfunction "GPIO10/SPI0_MOSI_P1_19") (pintype "bidirectional"))
      (node (ref "J2") (pin "7") (pinfunction "7_7") (pintype "passive"))
      (node (ref "J3") (pin "8") (pinfunction "8_8") (pintype "passive"))
      (node (ref "J4") (pin "8") (pinfunction "8_8") (pintype "bidirectional"))
    )
    (net (code "51") (name "SPI_SCLK") (class "Default")
      (node (ref "J1") (pin "P1_23") (pinfunction "GPIO11/SPI0_SLCK_P1_23") (pintype "bidirectional"))
      (node (ref "J2") (pin "8") (pinfunction "8_8") (pintype "passive"))
      (node (ref "J3") (pin "7") (pinfunction "7_7") (pintype "passive"))
      (node (ref "J4") (pin "7") (pinfunction "7_7") (pintype "bidirectional"))
    )
    (net (code "52") (name "TS") (class "Default")
      (node (ref "R28") (pin "2") (pinfunction "2_2") (pintype "passive"))
      (node (ref "R29") (pin "1") (pinfunction "1_1") (pintype "passive"))
      (node (ref "SJ1") (pin "1") (pinfunction "1_1") (pintype "passive"))
      (node (ref "TEMP") (pin "1") (pinfunction "TP_1") (pintype "passive"))
      (node (ref "U3") (pin "1") (pinfunction "TS_1") (pintype "bidirectional"))
    )
    (net (code "53") (name "TS_GAUGE") (class "Default")
      (node (ref "R20") (pin "1") (pinfunction "1_1") (pintype "passive"))
      (node (ref "R21") (pin "1") (pinfunction "1_1") (pintype "passive"))
      (node (ref "SJ1") (pin "2") (pinfunction "2_2") (pintype "passive"))
    )
    (net (code "54") (name "VBAT") (class "Default")
      (node (ref "C13") (pin "1") (pinfunction "1_1") (pintype "passive"))
      (node (ref "C19") (pin "1") (pinfunction "1_1") (pintype "passive"))
      (node (ref "J8") (pin "1") (pinfunction "2_1") (pintype "passive"))
      (node (ref "U2") (pin "3") (pinfunction "REGIN_3") (pintype "power_in"))
      (node (ref "U2") (pin "4") (pinfunction "BAT_4") (pintype "input"))
      (node (ref "U3") (pin "2") (pinfunction "BAT_2_2") (pintype "bidirectional"))
      (node (ref "U3") (pin "3") (pinfunction "BAT_3") (pintype "bidirectional"))
    )
    (net (code "55") (name "VBAT_NEG") (class "Default")
      (node (ref "J8") (pin "2") (pinfunction "1_2") (pintype "passive"))
      (node (ref "R14") (pin "2") (pinfunction "2_2") (pintype "passive"))
      (node (ref "R15") (pin "1") (pinfunction "1_1") (pintype "passive"))
    )
    (net (code "56") (name "VBAT_SW") (class "Default")
      (node (ref "C1") (pin "1") (pinfunction "1_1") (pintype "passive"))
      (node (ref "C5") (pin "1") (pinfunction "1_1") (pintype "passive"))
      (node (ref "L1") (pin "P$1") (pinfunction "1_P$1") (pintype "passive"))
      (node (ref "L1") (pin "P$2") (pinfunction "1_P$2") (pintype "passive"))
      (node (ref "Q1") (pin "5") (pinfunction "P-D2_5") (pintype "passive"))
      (node (ref "Q1") (pin "6") (pinfunction "P-D2_6") (pintype "passive"))
      (node (ref "R2") (pin "2") (pinfunction "2_2") (pintype "passive"))
      (node (ref "R9") (pin "1") (pinfunction "1_1") (pintype "passive"))
      (node (ref "U1") (pin "11") (pinfunction "EN_11") (pintype "input"))
      (node (ref "U1") (pin "8") (pinfunction "VBAT_8") (pintype "input"))
    )
    (net (code "57") (name "unconnected-(U1-FB-Pad14)") (class "Default")
      (node (ref "U1") (pin "14") (pinfunction "FB_14") (pintype "input"))
    )
    (net (code "58") (name "unconnected-(U1-NC-Pad2)") (class "Default")
      (node (ref "U1") (pin "2") (pinfunction "NC_2") (pintype "no_connect"))
    )
  )
)
